# Power.net
KiCad netlist of a schematic drawn in Altium Designer
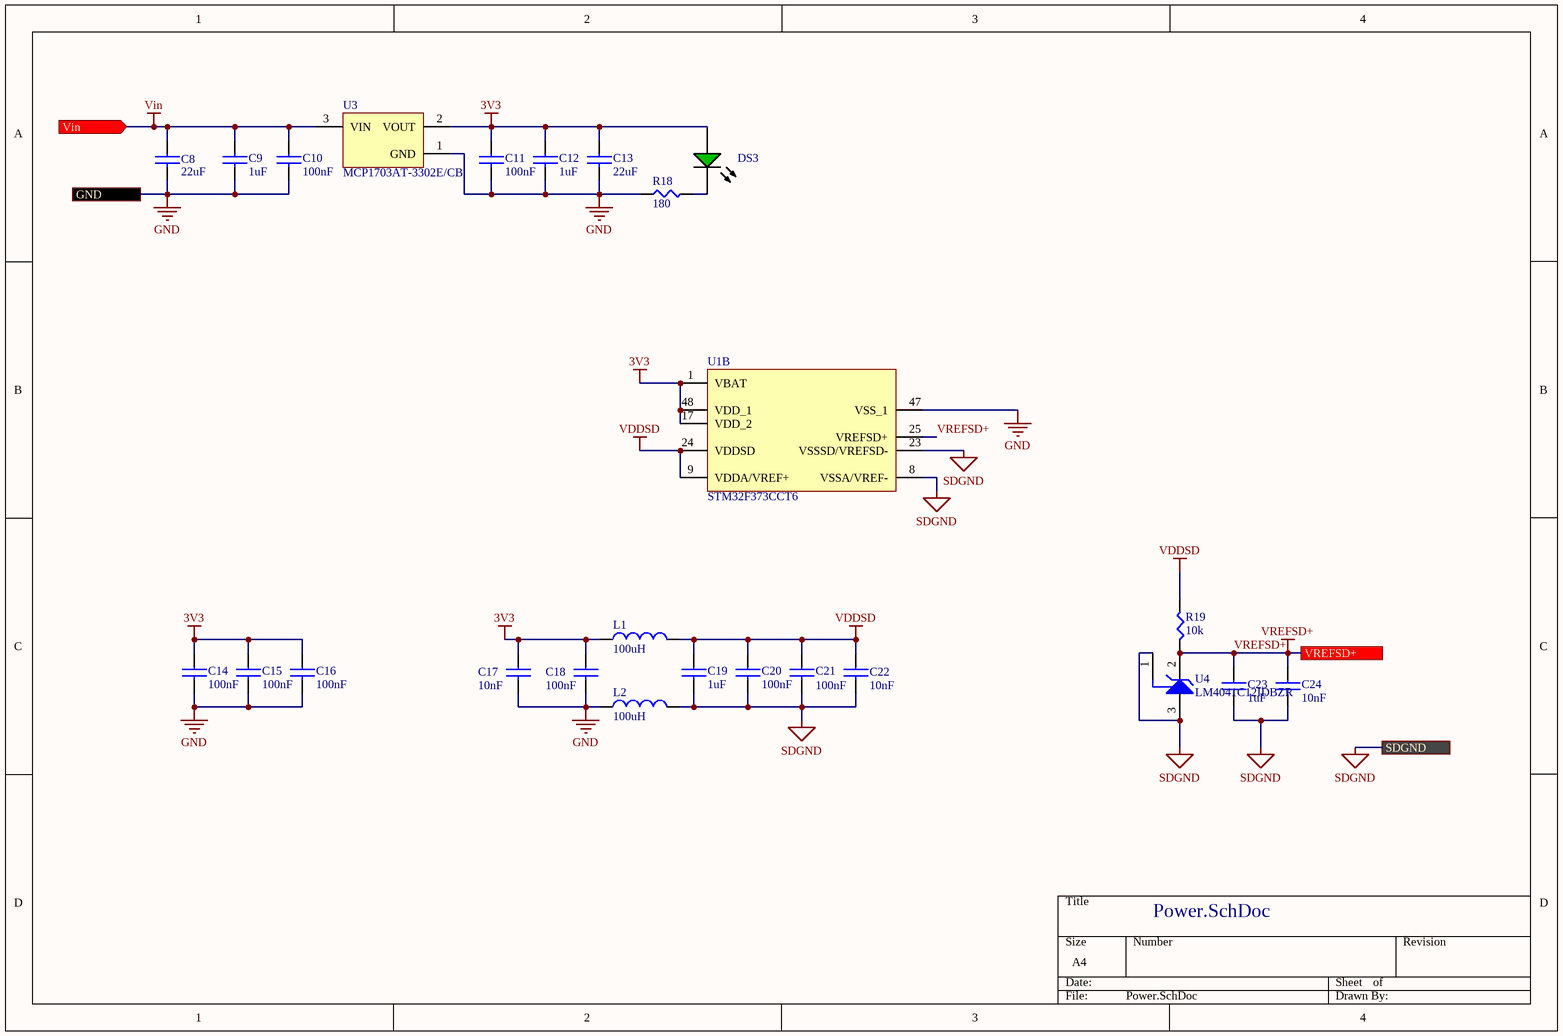
[diagram p0: Power.SchDoc]

(export (version "E")
  (design (tool "Eeschema 10.0.6"))
  (components
    (comp (ref "C8")
      (value "22uF")
      (footprint "CAPC200X125X110L50N")
      (fields (field (name "LCSC PART #") "C45783") (field (name "PART NUMBER") "CL21A226MAQNNNE"))
      (libsource (lib "Miscellaneous") (part "capacitor"))
    )
    (comp (ref "C9")
      (value "1uF")
      (footprint "CAPC160X80X90L35N")
      (fields (field (name "PART NUMBER") "CL10A105KB8NNNC") (field (name "LCSC PART #") "C15849"))
      (libsource (lib "Miscellaneous") (part "capacitor"))
    )
    (comp (ref "C10")
      (value "100nF")
      (footprint "CAPC160X80X90L35N")
      (fields (field (name "LCSC PART #") "C14663") (field (name "PART NUMBER") "CC0603KRX7R9BB104"))
      (libsource (lib "Miscellaneous") (part "capacitor"))
    )
    (comp (ref "C11")
      (value "100nF")
      (footprint "CAPC160X80X90L35N")
      (fields (field (name "LCSC PART #") "C14663") (field (name "PART NUMBER") "CC0603KRX7R9BB104"))
      (libsource (lib "Miscellaneous") (part "capacitor"))
    )
    (comp (ref "C12")
      (value "1uF")
      (footprint "CAPC160X80X90L35N")
      (fields (field (name "PART NUMBER") "CL10A105KB8NNNC") (field (name "LCSC PART #") "C15849"))
      (libsource (lib "Miscellaneous") (part "capacitor"))
    )
    (comp (ref "C13")
      (value "22uF")
      (footprint "CAPC200X125X110L50N")
      (fields (field (name "LCSC PART #") "C45783") (field (name "PART NUMBER") "CL21A226MAQNNNE"))
      (libsource (lib "Miscellaneous") (part "capacitor"))
    )
    (comp (ref "C14")
      (value "100nF")
      (footprint "CAPC160X80X90L35N")
      (fields (field (name "LCSC PART #") "C14663") (field (name "PART NUMBER") "CC0603KRX7R9BB104"))
      (libsource (lib "Miscellaneous") (part "capacitor"))
    )
    (comp (ref "C15")
      (value "100nF")
      (footprint "CAPC160X80X90L35N")
      (fields (field (name "LCSC PART #") "C14663") (field (name "PART NUMBER") "CC0603KRX7R9BB104"))
      (libsource (lib "Miscellaneous") (part "capacitor"))
    )
    (comp (ref "C16")
      (value "100nF")
      (footprint "CAPC160X80X90L35N")
      (fields (field (name "LCSC PART #") "C14663") (field (name "PART NUMBER") "CC0603KRX7R9BB104"))
      (libsource (lib "Miscellaneous") (part "capacitor"))
    )
    (comp (ref "C17")
      (value "10nF")
      (footprint "CAPC160X80X90L35N")
      (fields (field (name "LCSC PART #") "C57112") (field (name "PART NUMBER") "0603B103K500NT"))
      (libsource (lib "Miscellaneous") (part "capacitor"))
    )
    (comp (ref "C18")
      (value "100nF")
      (footprint "CAPC160X80X90L35N")
      (fields (field (name "LCSC PART #") "C14663") (field (name "PART NUMBER") "CC0603KRX7R9BB104"))
      (libsource (lib "Miscellaneous") (part "capacitor"))
    )
    (comp (ref "C19")
      (value "1uF")
      (footprint "CAPC160X80X90L35N")
      (fields (field (name "PART NUMBER") "CL10A105KB8NNNC") (field (name "LCSC PART #") "C15849"))
      (libsource (lib "Miscellaneous") (part "capacitor"))
    )
    (comp (ref "C20")
      (value "100nF")
      (footprint "CAPC160X80X90L35N")
      (fields (field (name "LCSC PART #") "C14663") (field (name "PART NUMBER") "CC0603KRX7R9BB104"))
      (libsource (lib "Miscellaneous") (part "capacitor"))
    )
    (comp (ref "C21")
      (value "100nF")
      (footprint "CAPC160X80X90L35N")
      (fields (field (name "LCSC PART #") "C14663") (field (name "PART NUMBER") "CC0603KRX7R9BB104"))
      (libsource (lib "Miscellaneous") (part "capacitor"))
    )
    (comp (ref "C22")
      (value "10nF")
      (footprint "CAPC160X80X90L35N")
      (fields (field (name "LCSC PART #") "C57112") (field (name "PART NUMBER") "0603B103K500NT"))
      (libsource (lib "Miscellaneous") (part "capacitor"))
    )
    (comp (ref "C23")
      (value "1uF")
      (footprint "CAPC160X80X90L35N")
      (fields (field (name "PART NUMBER") "CL10A105KB8NNNC") (field (name "LCSC PART #") "C15849"))
      (libsource (lib "Miscellaneous") (part "capacitor"))
    )
    (comp (ref "C24")
      (value "10nF")
      (footprint "CAPC160X80X90L35N")
      (fields (field (name "LCSC PART #") "C57112") (field (name "PART NUMBER") "0603B103K500NT"))
      (libsource (lib "Miscellaneous") (part "capacitor"))
    )
    (comp (ref "DS3")
      (value "19-217/GHC-YR1S2/3T")
      (footprint "LEDC160X80X60L30N")
      (description "Green LED")
      (fields (field (name "LCSC PART #") "C72043"))
      (libsource (lib "Miscellaneous") (part "LED"))
    )
    (comp (ref "L1")
      (value "100uH")
      (footprint "INDM320X250X240L55X190N")
      (description "Inductor")
      (fields (field (name "LCSC PART #") "C76836") (field (name "PART NUMBER") "NLV32T-101J-PF"))
      (libsource (lib "Miscellaneous") (part "Inductor"))
    )
    (comp (ref "L2")
      (value "100uH")
      (footprint "INDM320X250X240L55X190N")
      (description "Inductor")
      (fields (field (name "LCSC PART #") "C76836") (field (name "PART NUMBER") "NLV32T-101J-PF"))
      (libsource (lib "Miscellaneous") (part "Inductor"))
    )
    (comp (ref "R18")
      (value "180")
      (footprint "RESC160X80X90L30N")
      (fields (field (name "PART NUMBER") "0603WAF1800T5E") (field (name "LCSC PART #") "C22828"))
      (libsource (lib "Miscellaneous") (part "Resistor"))
    )
    (comp (ref "R19")
      (value "10k")
      (footprint "RESC160X80X90L30N")
      (fields (field (name "PART NUMBER") "0603WAF1002T5E") (field (name "LCSC PART #") "C25804"))
      (libsource (lib "Miscellaneous") (part "Resistor"))
    )
    (comp (ref "U1")
      (value "STM32F373CCT6")
      (footprint "STM-LQFP48_L")
      (fields (field (name "LCSC PART #") "C89403") (field (name "MANUFACTURER") "STMicroelectronics"))
      (libsource (lib "Miscellaneous") (part "STM32F373CCT6"))
    )
    (comp (ref "U3")
      (value "MCP1703AT-3302E/CB")
      (footprint "SOT-23A-CB3_M")
      (fields (field (name "PART NUMBER") "MCP1703") (field (name "LCSC PART #") "C144183"))
      (libsource (lib "Miscellaneous") (part "PM-LINEREG-MCP1703-IL3A"))
    )
    (comp (ref "U4")
      (value "LM4041C12IDBZR")
      (footprint "SOT-23A-CB3_M")
      (fields (field (name "MANUFACTURER") "Texas Instruments") (field (name "LCSC PART #") "C133587"))
      (libsource (lib "Miscellaneous") (part "LMZ4041C12IDBZR"))
    )
  )
  (nets
    (net (code "1") (name "3V3") (class "Default")
      (node (ref "C11") (pin "1") (pinfunction "1_1") (pintype "passive"))
      (node (ref "C12") (pin "1") (pinfunction "1_1") (pintype "passive"))
      (node (ref "C13") (pin "1") (pinfunction "1_1") (pintype "passive"))
      (node (ref "C14") (pin "1") (pinfunction "1_1") (pintype "passive"))
      (node (ref "C15") (pin "1") (pinfunction "1_1") (pintype "passive"))
      (node (ref "C16") (pin "1") (pinfunction "1_1") (pintype "passive"))
      (node (ref "C17") (pin "1") (pinfunction "1_1") (pintype "passive"))
      (node (ref "C18") (pin "1") (pinfunction "1_1") (pintype "passive"))
      (node (ref "DS3") (pin "A") (pinfunction "A_A") (pintype "passive"))
      (node (ref "L1") (pin "1") (pinfunction "1_1") (pintype "passive"))
      (node (ref "U1") (pin "1") (pinfunction "VBAT_1") (pintype "power_in"))
      (node (ref "U1") (pin "17") (pinfunction "VDD_2_17") (pintype "power_in"))
      (node (ref "U1") (pin "48") (pinfunction "VDD_1_48") (pintype "power_in"))
      (node (ref "U3") (pin "2") (pinfunction "VOUT_2") (pintype "power_in"))
    )
    (net (code "2") (name "GND") (class "Default")
      (node (ref "C10") (pin "2") (pinfunction "2_2") (pintype "passive"))
      (node (ref "C11") (pin "2") (pinfunction "2_2") (pintype "passive"))
      (node (ref "C12") (pin "2") (pinfunction "2_2") (pintype "passive"))
      (node (ref "C13") (pin "2") (pinfunction "2_2") (pintype "passive"))
      (node (ref "C14") (pin "2") (pinfunction "2_2") (pintype "passive"))
      (node (ref "C15") (pin "2") (pinfunction "2_2") (pintype "passive"))
      (node (ref "C16") (pin "2") (pinfunction "2_2") (pintype "passive"))
      (node (ref "C17") (pin "2") (pinfunction "2_2") (pintype "passive"))
      (node (ref "C18") (pin "2") (pinfunction "2_2") (pintype "passive"))
      (node (ref "C8") (pin "2") (pinfunction "2_2") (pintype "passive"))
      (node (ref "C9") (pin "2") (pinfunction "2_2") (pintype "passive"))
      (node (ref "L2") (pin "1") (pinfunction "1_1") (pintype "passive"))
      (node (ref "R18") (pin "1") (pinfunction "1_1") (pintype "passive"))
      (node (ref "U1") (pin "47") (pinfunction "VSS_1_47") (pintype "power_in"))
      (node (ref "U3") (pin "1") (pinfunction "GND_1") (pintype "power_in"))
    )
    (net (code "3") (name "Net-(DS3-PadC)") (class "Default")
      (node (ref "DS3") (pin "C") (pinfunction "C_C") (pintype "passive"))
      (node (ref "R18") (pin "2") (pinfunction "2_2") (pintype "passive"))
    )
    (net (code "4") (name "SDGND") (class "Default")
      (node (ref "C19") (pin "2") (pinfunction "2_2") (pintype "passive"))
      (node (ref "C20") (pin "2") (pinfunction "2_2") (pintype "passive"))
      (node (ref "C21") (pin "2") (pinfunction "2_2") (pintype "passive"))
      (node (ref "C22") (pin "2") (pinfunction "2_2") (pintype "passive"))
      (node (ref "C23") (pin "2") (pinfunction "2_2") (pintype "passive"))
      (node (ref "C24") (pin "2") (pinfunction "2_2") (pintype "passive"))
      (node (ref "L2") (pin "2") (pinfunction "2_2") (pintype "passive"))
      (node (ref "U1") (pin "23") (pinfunction "VSSSD/VREFSD-_23") (pintype "power_in"))
      (node (ref "U1") (pin "8") (pinfunction "VSSA/VREF-_8") (pintype "power_in"))
      (node (ref "U4") (pin "1") (pinfunction "CATHODE_1") (pintype "passive"))
      (node (ref "U4") (pin "3") (pinfunction "NC_3") (pintype "passive"))
    )
    (net (code "5") (name "VDDSD") (class "Default")
      (node (ref "C19") (pin "1") (pinfunction "1_1") (pintype "passive"))
      (node (ref "C20") (pin "1") (pinfunction "1_1") (pintype "passive"))
      (node (ref "C21") (pin "1") (pinfunction "1_1") (pintype "passive"))
      (node (ref "C22") (pin "1") (pinfunction "1_1") (pintype "passive"))
      (node (ref "L1") (pin "2") (pinfunction "2_2") (pintype "passive"))
      (node (ref "R19") (pin "2") (pinfunction "2_2") (pintype "passive"))
      (node (ref "U1") (pin "24") (pinfunction "VDDSD_24") (pintype "power_in"))
      (node (ref "U1") (pin "9") (pinfunction "VDDA/VREF+_9") (pintype "power_in"))
    )
    (net (code "6") (name "VREFSD+") (class "Default")
      (node (ref "C23") (pin "1") (pinfunction "1_1") (pintype "passive"))
      (node (ref "C24") (pin "1") (pinfunction "1_1") (pintype "passive"))
      (node (ref "R19") (pin "1") (pinfunction "1_1") (pintype "passive"))
      (node (ref "U1") (pin "25") (pinfunction "VREFSD+_25") (pintype "power_in"))
      (node (ref "U4") (pin "2") (pinfunction "ANODE_2") (pintype "passive"))
    )
    (net (code "7") (name "Vin") (class "Default")
      (node (ref "C10") (pin "1") (pinfunction "1_1") (pintype "passive"))
      (node (ref "C8") (pin "1") (pinfunction "1_1") (pintype "passive"))
      (node (ref "C9") (pin "1") (pinfunction "1_1") (pintype "passive"))
      (node (ref "U3") (pin "3") (pinfunction "VIN_3") (pintype "power_in"))
    )
  )
)
